# Sensors.net
KiCad netlist of a schematic drawn in Altium Designer
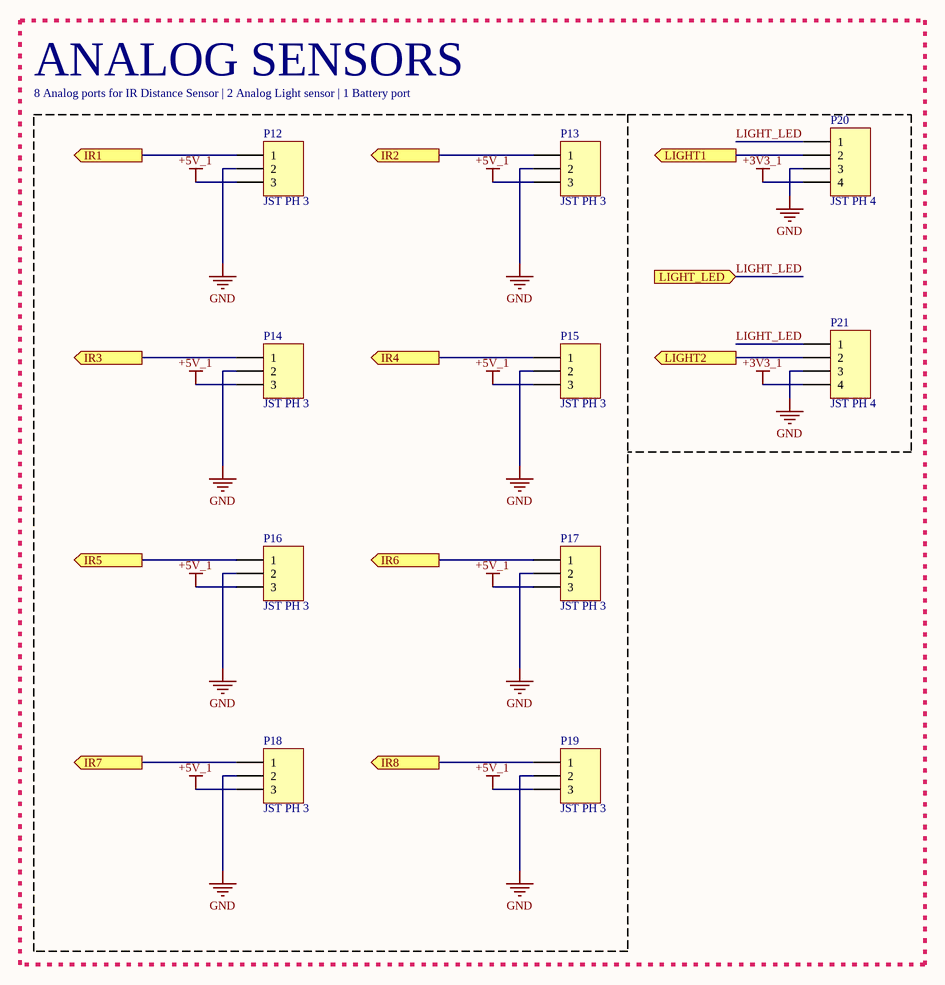
[diagram p0: Sensors.SchDoc]

(export (version "E")
  (design (tool "Eeschema 10.0.6"))
  (components
    (comp (ref "P12")
      (value "JST PH 3")
      (footprint "B3B-PH-K")
      (libsource (lib "CustomLibrary") (part "JST PH 3"))
    )
    (comp (ref "P13")
      (value "JST PH 3")
      (footprint "B3B-PH-K")
      (libsource (lib "CustomLibrary") (part "JST PH 3"))
    )
    (comp (ref "P14")
      (value "JST PH 3")
      (footprint "B3B-PH-K")
      (libsource (lib "CustomLibrary") (part "JST PH 3"))
    )
    (comp (ref "P15")
      (value "JST PH 3")
      (footprint "B3B-PH-K")
      (libsource (lib "CustomLibrary") (part "JST PH 3"))
    )
    (comp (ref "P16")
      (value "JST PH 3")
      (footprint "B3B-PH-K")
      (libsource (lib "CustomLibrary") (part "JST PH 3"))
    )
    (comp (ref "P17")
      (value "JST PH 3")
      (footprint "B3B-PH-K")
      (libsource (lib "CustomLibrary") (part "JST PH 3"))
    )
    (comp (ref "P18")
      (value "JST PH 3")
      (footprint "B3B-PH-K")
      (libsource (lib "CustomLibrary") (part "JST PH 3"))
    )
    (comp (ref "P19")
      (value "JST PH 3")
      (footprint "B3B-PH-K")
      (libsource (lib "CustomLibrary") (part "JST PH 3"))
    )
    (comp (ref "P20")
      (value "JST PH 4")
      (footprint "B4B-PH-K")
      (libsource (lib "CustomLibrary") (part "JST PH 4"))
    )
    (comp (ref "P21")
      (value "JST PH 4")
      (footprint "B4B-PH-K")
      (libsource (lib "CustomLibrary") (part "JST PH 4"))
    )
  )
  (nets
    (net (code "1") (name "+3V3_1") (class "Default")
      (node (ref "P20") (pin "4") (pinfunction "4_4") (pintype "passive"))
      (node (ref "P21") (pin "4") (pinfunction "4_4") (pintype "passive"))
    )
    (net (code "2") (name "+5V_1") (class "Default")
      (node (ref "P12") (pin "3") (pinfunction "3_3") (pintype "passive"))
      (node (ref "P13") (pin "3") (pinfunction "3_3") (pintype "passive"))
      (node (ref "P14") (pin "3") (pinfunction "3_3") (pintype "passive"))
      (node (ref "P15") (pin "3") (pinfunction "3_3") (pintype "passive"))
      (node (ref "P16") (pin "3") (pinfunction "3_3") (pintype "passive"))
      (node (ref "P17") (pin "3") (pinfunction "3_3") (pintype "passive"))
      (node (ref "P18") (pin "3") (pinfunction "3_3") (pintype "passive"))
      (node (ref "P19") (pin "3") (pinfunction "3_3") (pintype "passive"))
    )
    (net (code "3") (name "/IR1") (class "Default")
      (node (ref "P12") (pin "1") (pinfunction "1_1") (pintype "passive"))
    )
    (net (code "4") (name "/IR2") (class "Default")
      (node (ref "P13") (pin "1") (pinfunction "1_1") (pintype "passive"))
    )
    (net (code "5") (name "/IR3") (class "Default")
      (node (ref "P14") (pin "1") (pinfunction "1_1") (pintype "passive"))
    )
    (net (code "6") (name "/IR4") (class "Default")
      (node (ref "P15") (pin "1") (pinfunction "1_1") (pintype "passive"))
    )
    (net (code "7") (name "/IR5") (class "Default")
      (node (ref "P16") (pin "1") (pinfunction "1_1") (pintype "passive"))
    )
    (net (code "8") (name "/IR6") (class "Default")
      (node (ref "P17") (pin "1") (pinfunction "1_1") (pintype "passive"))
    )
    (net (code "9") (name "/IR7") (class "Default")
      (node (ref "P18") (pin "1") (pinfunction "1_1") (pintype "passive"))
    )
    (net (code "10") (name "/IR8") (class "Default")
      (node (ref "P19") (pin "1") (pinfunction "1_1") (pintype "passive"))
    )
    (net (code "11") (name "/LIGHT1") (class "Default")
      (node (ref "P20") (pin "2") (pinfunction "2_2") (pintype "passive"))
    )
    (net (code "12") (name "/LIGHT2") (class "Default")
      (node (ref "P21") (pin "2") (pinfunction "2_2") (pintype "passive"))
    )
    (net (code "13") (name "/LIGHT_LED") (class "Default")
      (node (ref "P20") (pin "1") (pinfunction "1_1") (pintype "passive"))
      (node (ref "P21") (pin "1") (pinfunction "1_1") (pintype "passive"))
    )
    (net (code "14") (name "GND") (class "Default")
      (node (ref "P12") (pin "2") (pinfunction "2_2") (pintype "passive"))
      (node (ref "P13") (pin "2") (pinfunction "2_2") (pintype "passive"))
      (node (ref "P14") (pin "2") (pinfunction "2_2") (pintype "passive"))
      (node (ref "P15") (pin "2") (pinfunction "2_2") (pintype "passive"))
      (node (ref "P16") (pin "2") (pinfunction "2_2") (pintype "passive"))
      (node (ref "P17") (pin "2") (pinfunction "2_2") (pintype "passive"))
      (node (ref "P18") (pin "2") (pinfunction "2_2") (pintype "passive"))
      (node (ref "P19") (pin "2") (pinfunction "2_2") (pintype "passive"))
      (node (ref "P20") (pin "3") (pinfunction "3_3") (pintype "passive"))
      (node (ref "P21") (pin "3") (pinfunction "3_3") (pintype "passive"))
    )
  )
)
